# espnative-deadrail-2-8.net
KiCad netlist of a schematic drawn in EAGLE
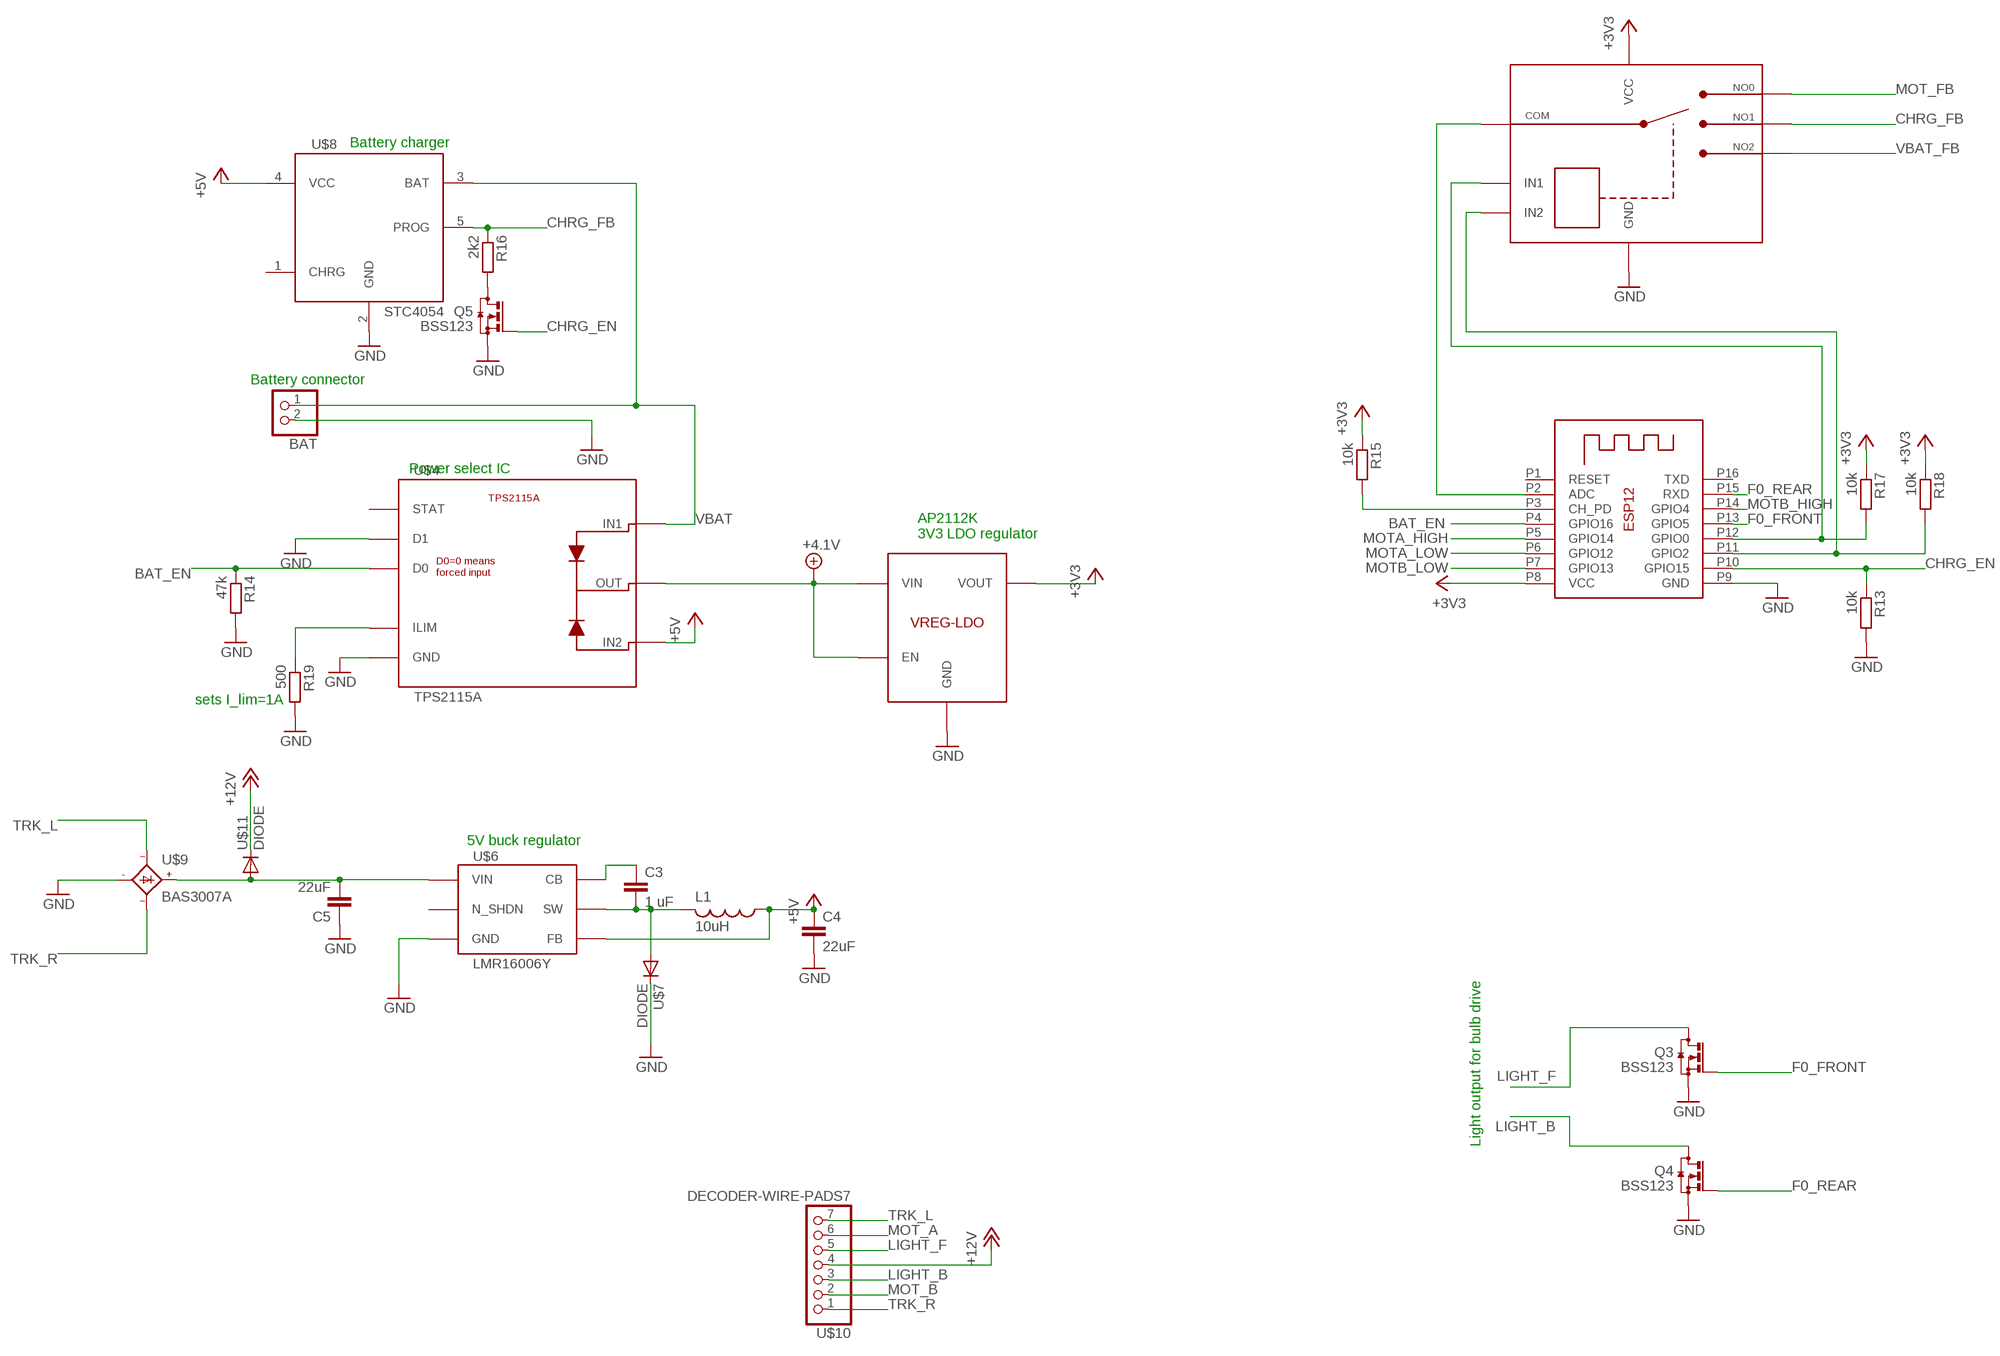
[diagram p0: schematic, sheet 1, part 1 of 2]
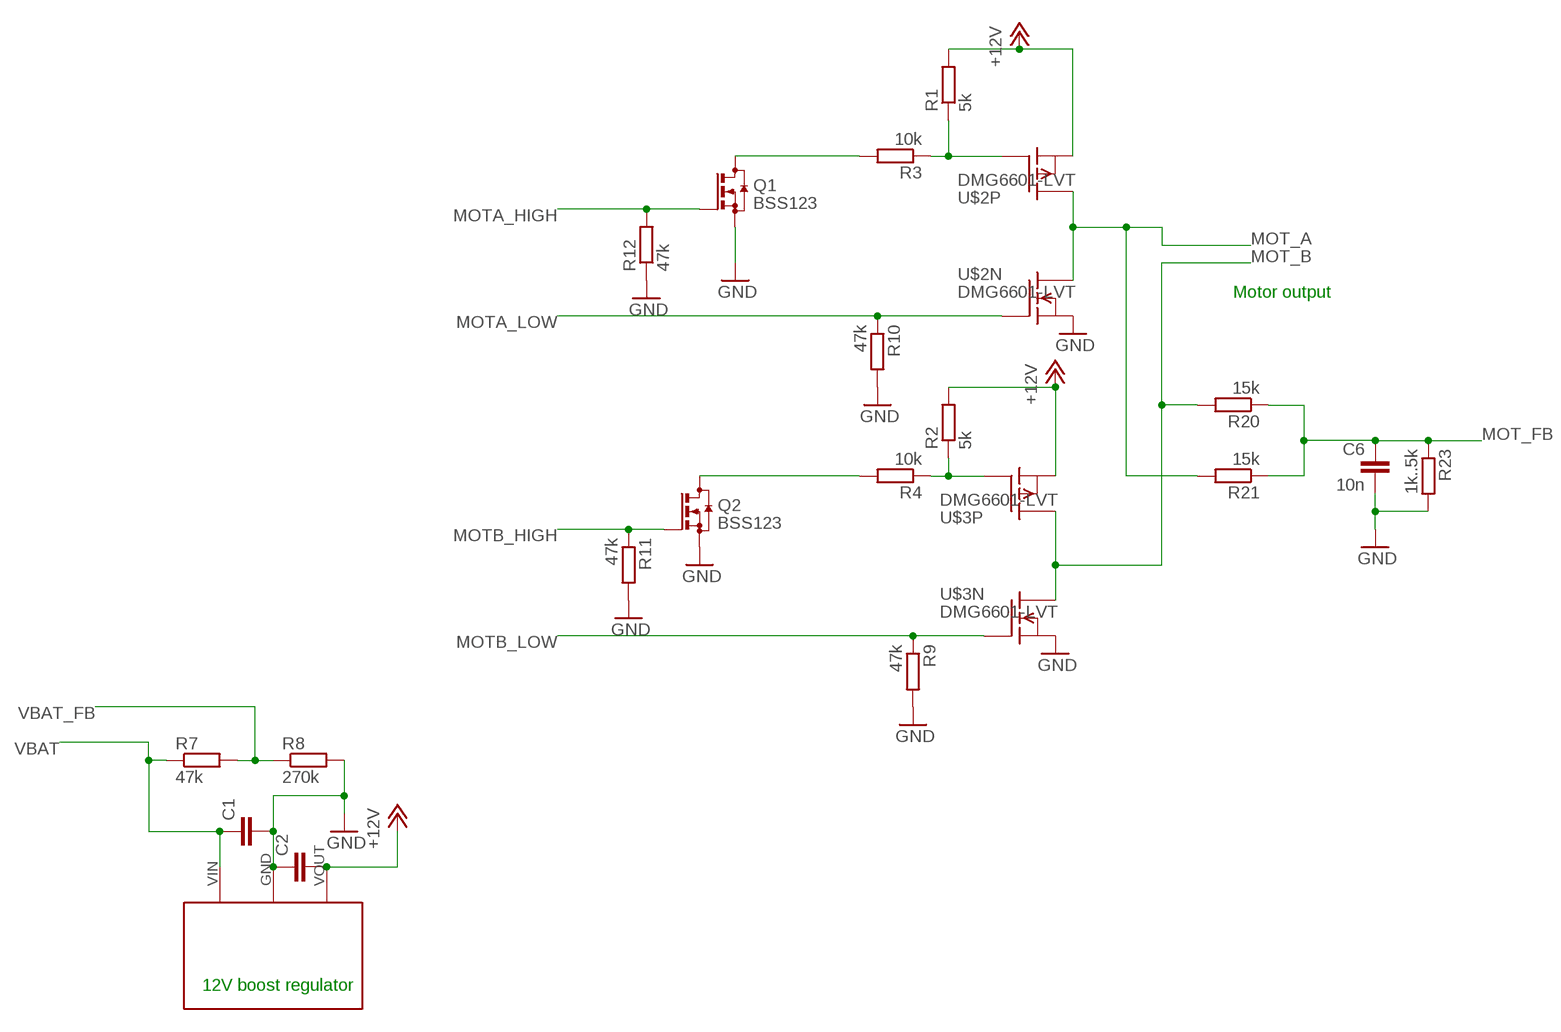
[diagram p1: schematic, sheet 1, part 2 of 2]

(export (version "E")
  (design (tool "Eeschema 10.0.6"))
  (components
    (comp (ref "BAT")
      (value "JST_2PIN-SMT-RA")
      (footprint "eagle-import:JST-PH-2-SMT-RA")
      (libsource (lib "eagle-import") (part "JST_2PIN-SMT-RA"))
    )
    (comp (ref "C1")
      (value "C-EUC1206")
      (footprint "eagle-import:C1206")
      (libsource (lib "eagle-import") (part "C-EUC1206"))
    )
    (comp (ref "C2")
      (value "C-EUC1206")
      (footprint "eagle-import:C1206")
      (libsource (lib "eagle-import") (part "C-EUC1206"))
    )
    (comp (ref "C3")
      (value "1 uF")
      (footprint "eagle-import:C0603")
      (libsource (lib "eagle-import") (part "C-EUC0603"))
    )
    (comp (ref "C4")
      (value "22uF")
      (footprint "eagle-import:C0603")
      (libsource (lib "eagle-import") (part "C-EUC0603"))
    )
    (comp (ref "C5")
      (value "22uF")
      (footprint "eagle-import:C1206")
      (libsource (lib "eagle-import") (part "C-EUC1206"))
    )
    (comp (ref "C6")
      (value "10n")
      (footprint "eagle-import:C0603")
      (libsource (lib "eagle-import") (part "C-EUC0603"))
    )
    (comp (ref "L1")
      (value "10uH")
      (footprint "eagle-import:FDSD0420")
      (libsource (lib "eagle-import") (part "FDSD0420"))
    )
    (comp (ref "Q1")
      (value "BSS123")
      (footprint "eagle-import:SOT23")
      (libsource (lib "eagle-import") (part "BSS123"))
    )
    (comp (ref "Q2")
      (value "BSS123")
      (footprint "eagle-import:SOT23")
      (libsource (lib "eagle-import") (part "BSS123"))
    )
    (comp (ref "Q3")
      (value "BSS123")
      (footprint "eagle-import:SOT23")
      (libsource (lib "eagle-import") (part "BSS123"))
    )
    (comp (ref "Q4")
      (value "BSS123")
      (footprint "eagle-import:SOT23")
      (libsource (lib "eagle-import") (part "BSS123"))
    )
    (comp (ref "Q5")
      (value "BSS123")
      (footprint "eagle-import:SOT23")
      (libsource (lib "eagle-import") (part "BSS123"))
    )
    (comp (ref "R1")
      (value "5k")
      (footprint "eagle-import:R0603")
      (libsource (lib "eagle-import") (part "R-EU_R0603"))
    )
    (comp (ref "R2")
      (value "5k")
      (footprint "eagle-import:R0603")
      (libsource (lib "eagle-import") (part "R-EU_R0603"))
    )
    (comp (ref "R3")
      (value "10k")
      (footprint "eagle-import:R0603")
      (libsource (lib "eagle-import") (part "R-EU_R0603"))
    )
    (comp (ref "R4")
      (value "10k")
      (footprint "eagle-import:R0603")
      (libsource (lib "eagle-import") (part "R-EU_R0603"))
    )
    (comp (ref "R7")
      (value "47k")
      (footprint "eagle-import:R0603")
      (libsource (lib "eagle-import") (part "R-EU_R0603"))
    )
    (comp (ref "R8")
      (value "270k")
      (footprint "eagle-import:R0603")
      (libsource (lib "eagle-import") (part "R-EU_R0603"))
    )
    (comp (ref "R9")
      (value "47k")
      (footprint "eagle-import:R0603")
      (libsource (lib "eagle-import") (part "R-EU_R0603"))
    )
    (comp (ref "R10")
      (value "47k")
      (footprint "eagle-import:R0603")
      (libsource (lib "eagle-import") (part "R-EU_R0603"))
    )
    (comp (ref "R11")
      (value "47k")
      (footprint "eagle-import:R0603")
      (libsource (lib "eagle-import") (part "R-EU_R0603"))
    )
    (comp (ref "R12")
      (value "47k")
      (footprint "eagle-import:R0603")
      (libsource (lib "eagle-import") (part "R-EU_R0603"))
    )
    (comp (ref "R13")
      (value "10k")
      (footprint "eagle-import:R0603")
      (libsource (lib "eagle-import") (part "R-EU_R0603"))
    )
    (comp (ref "R14")
      (value "47k")
      (footprint "eagle-import:R0603")
      (libsource (lib "eagle-import") (part "R-EU_R0603"))
    )
    (comp (ref "R15")
      (value "10k")
      (footprint "eagle-import:R0603")
      (libsource (lib "eagle-import") (part "R-EU_R0603"))
    )
    (comp (ref "R16")
      (value "2k2")
      (footprint "eagle-import:R0603")
      (libsource (lib "eagle-import") (part "R-EU_R0603"))
    )
    (comp (ref "R17")
      (value "10k")
      (footprint "eagle-import:R0603")
      (libsource (lib "eagle-import") (part "R-EU_R0603"))
    )
    (comp (ref "R18")
      (value "10k")
      (footprint "eagle-import:R0603")
      (libsource (lib "eagle-import") (part "R-EU_R0603"))
    )
    (comp (ref "R19")
      (value "500")
      (footprint "eagle-import:R0603")
      (libsource (lib "eagle-import") (part "R-EU_R0603"))
    )
    (comp (ref "R20")
      (value "15k")
      (footprint "eagle-import:R0603")
      (libsource (lib "eagle-import") (part "R-EU_R0603"))
    )
    (comp (ref "R21")
      (value "15k")
      (footprint "eagle-import:R0603")
      (libsource (lib "eagle-import") (part "R-EU_R0603"))
    )
    (comp (ref "R23")
      (value "1k..5k")
      (footprint "eagle-import:R0603")
      (libsource (lib "eagle-import") (part "R-EU_R0603"))
    )
    (comp (ref "U$1")
      (value "AP2112K-3V3")
      (footprint "eagle-import:SOT23-5L")
      (libsource (lib "eagle-import") (part "AP2112K"))
    )
    (comp (ref "U$2")
      (value "DMG6601-LVT")
      (footprint "eagle-import:TSOT-26")
      (libsource (lib "eagle-import") (part "DMG6601-LVT"))
    )
    (comp (ref "U$3")
      (value "DMG6601-LVT")
      (footprint "eagle-import:TSOT-26")
      (libsource (lib "eagle-import") (part "DMG6601-LVT"))
    )
    (comp (ref "U$4")
      (value "TPS2115A")
      (footprint "eagle-import:TSSOP-8")
      (libsource (lib "eagle-import") (part "TPS2115A"))
    )
    (comp (ref "U$5")
      (value "POLOLU-VREG12")
      (footprint "eagle-import:POLOLU-REGULATOR")
      (libsource (lib "eagle-import") (part "POLOLU-VREG12"))
    )
    (comp (ref "U$6")
      (value "LMR16006Y")
      (footprint "eagle-import:SOT23-6")
      (libsource (lib "eagle-import") (part "LMR16006Y"))
    )
    (comp (ref "U$7")
      (value "DIODE")
      (footprint "eagle-import:DIODE-1206")
      (libsource (lib "eagle-import") (part "DIODE"))
    )
    (comp (ref "U$8")
      (value "STC4054")
      (footprint "eagle-import:SOT23-5L")
      (libsource (lib "eagle-import") (part "STC4054"))
    )
    (comp (ref "U$9")
      (value "BAS3007A")
      (footprint "eagle-import:SOT143B")
      (libsource (lib "eagle-import") (part "BAS3007A"))
    )
    (comp (ref "U$10")
      (value "DECODER-WIRE-PADS7")
      (footprint "eagle-import:DECODER-WIRE-PADS")
      (libsource (lib "eagle-import") (part "DECODER-WIRE-PADS7"))
    )
    (comp (ref "U$11")
      (value "DIODE")
      (footprint "eagle-import:DIODE-1206")
      (libsource (lib "eagle-import") (part "DIODE"))
    )
    (comp (ref "U$12")
      (value "TS5A3359")
      (footprint "eagle-import:US8")
      (libsource (lib "eagle-import") (part "TS5A3359"))
    )
    (comp (ref "X1")
      (value "ESP-12-TH")
      (footprint "eagle-import:ESP-12-TH")
      (libsource (lib "eagle-import") (part "ESP-12-TH"))
    )
  )
  (nets
    (net (code "1") (name "+3V3") (class "Default")
      (node (ref "R15") (pin "1") (pinfunction "1_1") (pintype "passive"))
      (node (ref "R17") (pin "1") (pinfunction "1_1") (pintype "passive"))
      (node (ref "R18") (pin "1") (pinfunction "1_1") (pintype "passive"))
      (node (ref "U$1") (pin "5") (pinfunction "VOUT_5") (pintype "bidirectional"))
      (node (ref "U$12") (pin "8") (pinfunction "VCC_8") (pintype "bidirectional"))
      (node (ref "X1") (pin "P8") (pinfunction "VCC_P8") (pintype "power_in"))
    )
    (net (code "2") (name "+4.1V") (class "Default")
      (node (ref "U$1") (pin "1") (pinfunction "VIN_1") (pintype "bidirectional"))
      (node (ref "U$1") (pin "3") (pinfunction "EN_3") (pintype "bidirectional"))
      (node (ref "U$4") (pin "7") (pinfunction "OUT_7") (pintype "bidirectional"))
    )
    (net (code "3") (name "+5V") (class "Default")
      (node (ref "C4") (pin "1") (pinfunction "1_1") (pintype "passive"))
      (node (ref "L1") (pin "P$1") (pinfunction "1_P$1") (pintype "passive"))
      (node (ref "U$4") (pin "6") (pinfunction "IN2_6") (pintype "bidirectional"))
      (node (ref "U$6") (pin "3") (pinfunction "FB_3") (pintype "bidirectional"))
      (node (ref "U$8") (pin "4") (pinfunction "VCC_4") (pintype "bidirectional"))
    )
    (net (code "4") (name "+12V") (class "Default")
      (node (ref "C2") (pin "2") (pinfunction "2_2") (pintype "passive"))
      (node (ref "R1") (pin "2") (pinfunction "2_2") (pintype "passive"))
      (node (ref "R2") (pin "2") (pinfunction "2_2") (pintype "passive"))
      (node (ref "U$10") (pin "4") (pinfunction "4_4") (pintype "passive"))
      (node (ref "U$11") (pin "C") (pinfunction "C_C") (pintype "passive"))
      (node (ref "U$2") (pin "2") (pinfunction "S_2") (pintype "passive"))
      (node (ref "U$3") (pin "2") (pinfunction "S_2") (pintype "passive"))
      (node (ref "U$5") (pin "VOUT") (pinfunction "VOUT_VOUT") (pintype "bidirectional"))
    )
    (net (code "5") (name "/BAT_EN") (class "Default")
      (node (ref "R14") (pin "1") (pinfunction "1_1") (pintype "passive"))
      (node (ref "U$4") (pin "2") (pinfunction "D0_2") (pintype "bidirectional"))
      (node (ref "X1") (pin "P4") (pinfunction "GPIO16_P4") (pintype "bidirectional"))
    )
    (net (code "6") (name "/CHRG_EN") (class "Default")
      (node (ref "Q5") (pin "1") (pinfunction "G_1") (pintype "passive"))
      (node (ref "R13") (pin "1") (pinfunction "1_1") (pintype "passive"))
      (node (ref "X1") (pin "P10") (pinfunction "GPIO15_P10") (pintype "bidirectional"))
    )
    (net (code "7") (name "/CHRG_FB") (class "Default")
      (node (ref "R16") (pin "1") (pinfunction "1_1") (pintype "passive"))
      (node (ref "U$12") (pin "2") (pinfunction "NO1_2") (pintype "bidirectional"))
      (node (ref "U$8") (pin "5") (pinfunction "PROG_5") (pintype "bidirectional"))
    )
    (net (code "8") (name "/F0_FRONT") (class "Default")
      (node (ref "Q3") (pin "1") (pinfunction "G_1") (pintype "passive"))
      (node (ref "X1") (pin "P13") (pinfunction "GPIO5_P13") (pintype "bidirectional"))
    )
    (net (code "9") (name "/F0_REAR") (class "Default")
      (node (ref "Q4") (pin "1") (pinfunction "G_1") (pintype "passive"))
      (node (ref "X1") (pin "P15") (pinfunction "RXD_P15") (pintype "input"))
    )
    (net (code "10") (name "/LIGHT_B") (class "Default")
      (node (ref "Q4") (pin "3") (pinfunction "D_3") (pintype "passive"))
      (node (ref "U$10") (pin "3") (pinfunction "3_3") (pintype "passive"))
    )
    (net (code "11") (name "/LIGHT_F") (class "Default")
      (node (ref "Q3") (pin "3") (pinfunction "D_3") (pintype "passive"))
      (node (ref "U$10") (pin "5") (pinfunction "5_5") (pintype "passive"))
    )
    (net (code "12") (name "/MOTA_HIGH") (class "Default")
      (node (ref "Q1") (pin "1") (pinfunction "G_1") (pintype "passive"))
      (node (ref "R12") (pin "2") (pinfunction "2_2") (pintype "passive"))
      (node (ref "X1") (pin "P5") (pinfunction "GPIO14_P5") (pintype "bidirectional"))
    )
    (net (code "13") (name "/MOTA_LOW") (class "Default")
      (node (ref "R10") (pin "1") (pinfunction "1_1") (pintype "passive"))
      (node (ref "U$2") (pin "1") (pinfunction "G_1") (pintype "passive"))
      (node (ref "X1") (pin "P6") (pinfunction "GPIO12_P6") (pintype "bidirectional"))
    )
    (net (code "14") (name "/MOTB_HIGH") (class "Default")
      (node (ref "Q2") (pin "1") (pinfunction "G_1") (pintype "passive"))
      (node (ref "R11") (pin "1") (pinfunction "1_1") (pintype "passive"))
      (node (ref "X1") (pin "P14") (pinfunction "GPIO4_P14") (pintype "bidirectional"))
    )
    (net (code "15") (name "/MOTB_LOW") (class "Default")
      (node (ref "R9") (pin "1") (pinfunction "1_1") (pintype "passive"))
      (node (ref "U$3") (pin "1") (pinfunction "G_1") (pintype "passive"))
      (node (ref "X1") (pin "P7") (pinfunction "GPIO13_P7") (pintype "bidirectional"))
    )
    (net (code "16") (name "/MOT_A") (class "Default")
      (node (ref "R21") (pin "2") (pinfunction "2_2") (pintype "passive"))
      (node (ref "U$10") (pin "6") (pinfunction "6_6") (pintype "passive"))
      (node (ref "U$2") (pin "4") (pinfunction "D_4") (pintype "passive"))
      (node (ref "U$2") (pin "6") (pinfunction "D_6") (pintype "passive"))
    )
    (net (code "17") (name "/MOT_B") (class "Default")
      (node (ref "R20") (pin "2") (pinfunction "2_2") (pintype "passive"))
      (node (ref "U$10") (pin "2") (pinfunction "2_2") (pintype "passive"))
      (node (ref "U$3") (pin "4") (pinfunction "D_4") (pintype "passive"))
      (node (ref "U$3") (pin "6") (pinfunction "D_6") (pintype "passive"))
    )
    (net (code "18") (name "/MOT_FB") (class "Default")
      (node (ref "C6") (pin "1") (pinfunction "1_1") (pintype "passive"))
      (node (ref "R20") (pin "1") (pinfunction "1_1") (pintype "passive"))
      (node (ref "R21") (pin "1") (pinfunction "1_1") (pintype "passive"))
      (node (ref "R23") (pin "1") (pinfunction "1_1") (pintype "passive"))
      (node (ref "U$12") (pin "1") (pinfunction "NO0_1") (pintype "bidirectional"))
    )
    (net (code "19") (name "/TRK_L") (class "Default")
      (node (ref "U$10") (pin "7") (pinfunction "7_7") (pintype "passive"))
      (node (ref "U$9") (pin "2") (pinfunction "AC1_2") (pintype "passive"))
    )
    (net (code "20") (name "/TRK_R") (class "Default")
      (node (ref "U$10") (pin "1") (pinfunction "1_1") (pintype "passive"))
      (node (ref "U$9") (pin "3") (pinfunction "AC2_3") (pintype "passive"))
    )
    (net (code "21") (name "/VBAT") (class "Default")
      (node (ref "BAT") (pin "1") (pinfunction "2_1") (pintype "passive"))
      (node (ref "C1") (pin "1") (pinfunction "1_1") (pintype "passive"))
      (node (ref "R7") (pin "1") (pinfunction "1_1") (pintype "passive"))
      (node (ref "U$4") (pin "8") (pinfunction "IN1_8") (pintype "bidirectional"))
      (node (ref "U$5") (pin "VIN") (pinfunction "VIN_VIN") (pintype "bidirectional"))
      (node (ref "U$8") (pin "3") (pinfunction "BAT_3") (pintype "bidirectional"))
    )
    (net (code "22") (name "/VBAT_FB") (class "Default")
      (node (ref "R7") (pin "2") (pinfunction "2_2") (pintype "passive"))
      (node (ref "R8") (pin "1") (pinfunction "1_1") (pintype "passive"))
      (node (ref "U$12") (pin "3") (pinfunction "NO2_3") (pintype "bidirectional"))
    )
    (net (code "23") (name "GND") (class "Default")
      (node (ref "BAT") (pin "2") (pinfunction "1_2") (pintype "passive"))
      (node (ref "C1") (pin "2") (pinfunction "2_2") (pintype "passive"))
      (node (ref "C2") (pin "1") (pinfunction "1_1") (pintype "passive"))
      (node (ref "C4") (pin "2") (pinfunction "2_2") (pintype "passive"))
      (node (ref "C5") (pin "1") (pinfunction "1_1") (pintype "passive"))
      (node (ref "C6") (pin "2") (pinfunction "2_2") (pintype "passive"))
      (node (ref "Q1") (pin "2") (pinfunction "S_2") (pintype "passive"))
      (node (ref "Q2") (pin "2") (pinfunction "S_2") (pintype "passive"))
      (node (ref "Q3") (pin "2") (pinfunction "S_2") (pintype "passive"))
      (node (ref "Q4") (pin "2") (pinfunction "S_2") (pintype "passive"))
      (node (ref "Q5") (pin "2") (pinfunction "S_2") (pintype "passive"))
      (node (ref "R10") (pin "2") (pinfunction "2_2") (pintype "passive"))
      (node (ref "R11") (pin "2") (pinfunction "2_2") (pintype "passive"))
      (node (ref "R12") (pin "1") (pinfunction "1_1") (pintype "passive"))
      (node (ref "R13") (pin "2") (pinfunction "2_2") (pintype "passive"))
      (node (ref "R14") (pin "2") (pinfunction "2_2") (pintype "passive"))
      (node (ref "R19") (pin "2") (pinfunction "2_2") (pintype "passive"))
      (node (ref "R23") (pin "2") (pinfunction "2_2") (pintype "passive"))
      (node (ref "R8") (pin "2") (pinfunction "2_2") (pintype "passive"))
      (node (ref "R9") (pin "2") (pinfunction "2_2") (pintype "passive"))
      (node (ref "U$1") (pin "2") (pinfunction "GND_2") (pintype "bidirectional"))
      (node (ref "U$12") (pin "4") (pinfunction "GND_4") (pintype "bidirectional"))
      (node (ref "U$2") (pin "5") (pinfunction "S_5") (pintype "passive"))
      (node (ref "U$3") (pin "5") (pinfunction "S_5") (pintype "passive"))
      (node (ref "U$4") (pin "3") (pinfunction "D1_3") (pintype "bidirectional"))
      (node (ref "U$4") (pin "5") (pinfunction "GND_5") (pintype "bidirectional"))
      (node (ref "U$5") (pin "GND") (pinfunction "GND_GND") (pintype "bidirectional"))
      (node (ref "U$6") (pin "2") (pinfunction "GND_2") (pintype "bidirectional"))
      (node (ref "U$7") (pin "C") (pinfunction "C_C") (pintype "passive"))
      (node (ref "U$8") (pin "2") (pinfunction "GND_2") (pintype "bidirectional"))
      (node (ref "U$9") (pin "1") (pinfunction "-_1") (pintype "passive"))
      (node (ref "X1") (pin "P9") (pinfunction "GND_P9") (pintype "power_in"))
    )
    (net (code "24") (name "Net-(L1-2)") (class "Default")
      (node (ref "C3") (pin "2") (pinfunction "2_2") (pintype "passive"))
      (node (ref "L1") (pin "P$2") (pinfunction "2_P$2") (pintype "passive"))
      (node (ref "U$6") (pin "6") (pinfunction "SW_6") (pintype "bidirectional"))
      (node (ref "U$7") (pin "A") (pinfunction "A_A") (pintype "passive"))
    )
    (net (code "25") (name "Net-(Q1-D)") (class "Default")
      (node (ref "Q1") (pin "3") (pinfunction "D_3") (pintype "passive"))
      (node (ref "R3") (pin "2") (pinfunction "2_2") (pintype "passive"))
    )
    (net (code "26") (name "Net-(Q2-D)") (class "Default")
      (node (ref "Q2") (pin "3") (pinfunction "D_3") (pintype "passive"))
      (node (ref "R4") (pin "2") (pinfunction "2_2") (pintype "passive"))
    )
    (net (code "27") (name "Net-(Q5-D)") (class "Default")
      (node (ref "Q5") (pin "3") (pinfunction "D_3") (pintype "passive"))
      (node (ref "R16") (pin "2") (pinfunction "2_2") (pintype "passive"))
    )
    (net (code "28") (name "Net-(U$2B-G)") (class "Default")
      (node (ref "R1") (pin "1") (pinfunction "1_1") (pintype "passive"))
      (node (ref "R3") (pin "1") (pinfunction "1_1") (pintype "passive"))
      (node (ref "U$2") (pin "3") (pinfunction "G_3") (pintype "passive"))
    )
    (net (code "29") (name "Net-(U$3B-G)") (class "Default")
      (node (ref "R2") (pin "1") (pinfunction "1_1") (pintype "passive"))
      (node (ref "R4") (pin "1") (pinfunction "1_1") (pintype "passive"))
      (node (ref "U$3") (pin "3") (pinfunction "G_3") (pintype "passive"))
    )
    (net (code "30") (name "Net-(U$4-ILIM)") (class "Default")
      (node (ref "R19") (pin "1") (pinfunction "1_1") (pintype "passive"))
      (node (ref "U$4") (pin "4") (pinfunction "ILIM_4") (pintype "bidirectional"))
    )
    (net (code "31") (name "Net-(U$6-CB)") (class "Default")
      (node (ref "C3") (pin "1") (pinfunction "1_1") (pintype "passive"))
      (node (ref "U$6") (pin "1") (pinfunction "CB_1") (pintype "bidirectional"))
    )
    (net (code "32") (name "Net-(U$6-VIN)") (class "Default")
      (node (ref "C5") (pin "2") (pinfunction "2_2") (pintype "passive"))
      (node (ref "U$11") (pin "A") (pinfunction "A_A") (pintype "passive"))
      (node (ref "U$6") (pin "5") (pinfunction "VIN_5") (pintype "bidirectional"))
      (node (ref "U$9") (pin "4") (pinfunction "+_4") (pintype "passive"))
    )
    (net (code "33") (name "Net-(U$12-COM)") (class "Default")
      (node (ref "U$12") (pin "7") (pinfunction "COM_7") (pintype "bidirectional"))
      (node (ref "X1") (pin "P2") (pinfunction "ADC_P2") (pintype "passive"))
    )
    (net (code "34") (name "Net-(U$12-IN1)") (class "Default")
      (node (ref "R17") (pin "2") (pinfunction "2_2") (pintype "passive"))
      (node (ref "U$12") (pin "6") (pinfunction "IN1_6") (pintype "bidirectional"))
      (node (ref "X1") (pin "P12") (pinfunction "GPIO0_P12") (pintype "bidirectional"))
    )
    (net (code "35") (name "Net-(U$12-IN2)") (class "Default")
      (node (ref "R18") (pin "2") (pinfunction "2_2") (pintype "passive"))
      (node (ref "U$12") (pin "5") (pinfunction "IN2_5") (pintype "bidirectional"))
      (node (ref "X1") (pin "P11") (pinfunction "GPIO2_P11") (pintype "bidirectional"))
    )
    (net (code "36") (name "Net-(X1-CH_PD)") (class "Default")
      (node (ref "R15") (pin "2") (pinfunction "2_2") (pintype "passive"))
      (node (ref "X1") (pin "P3") (pinfunction "CH_PD_P3") (pintype "input"))
    )
    (net (code "37") (name "unconnected-(U$4-STAT-Pad1)") (class "Default")
      (node (ref "U$4") (pin "1") (pinfunction "STAT_1") (pintype "bidirectional"))
    )
    (net (code "38") (name "unconnected-(U$6-N_SHDN-Pad4)") (class "Default")
      (node (ref "U$6") (pin "4") (pinfunction "N_SHDN_4") (pintype "bidirectional"))
    )
    (net (code "39") (name "unconnected-(U$8-CHRG-Pad1)") (class "Default")
      (node (ref "U$8") (pin "1") (pinfunction "CHRG_1") (pintype "bidirectional"))
    )
    (net (code "40") (name "unconnected-(X1-RESET-PadP1)") (class "Default")
      (node (ref "X1") (pin "P1") (pinfunction "RESET_P1") (pintype "input"))
    )
    (net (code "41") (name "unconnected-(X1-TXD-PadP16)") (class "Default")
      (node (ref "X1") (pin "P16") (pinfunction "TXD_P16") (pintype "output"))
    )
  )
)
